# FPSModule.net
KiCad netlist of a schematic drawn in Altium Designer
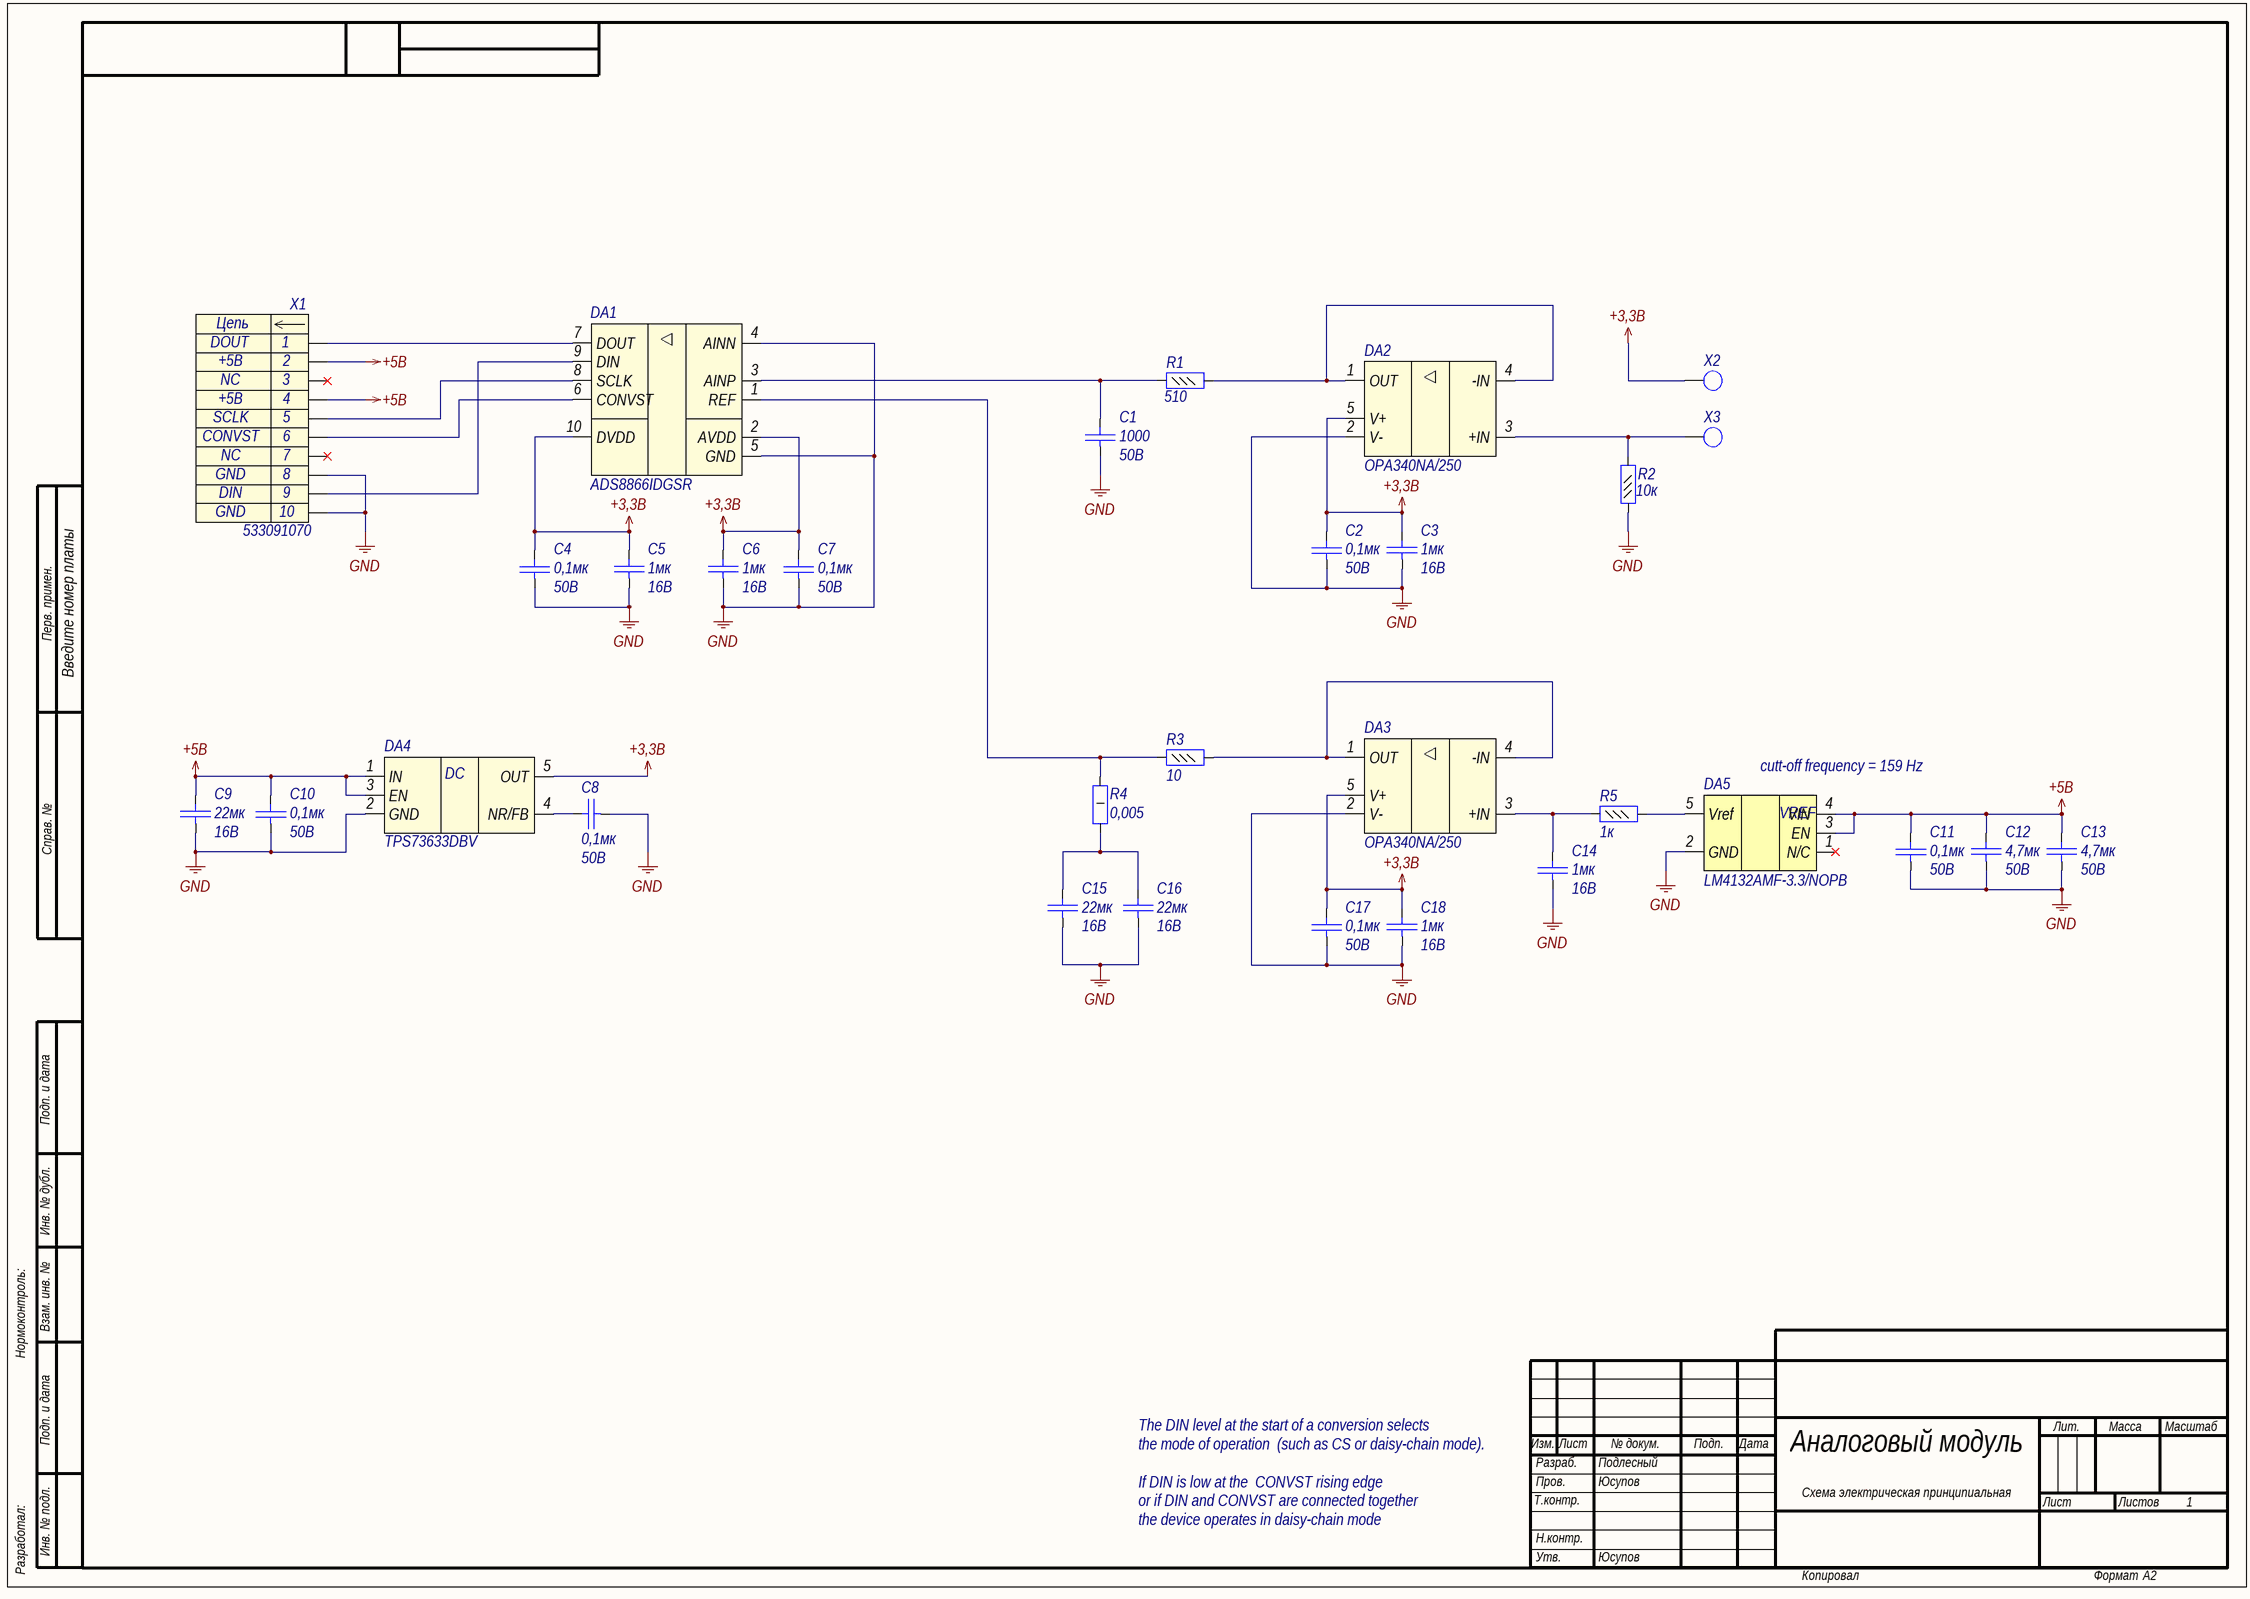
[diagram p0: FPSModule.SchDoc]

(export (version "E")
  (design (tool "Eeschema 10.0.6"))
  (components
    (comp (ref "C1")
      (value "1000")
      (footprint "C0402")
      (description "Конденсатор")
      (fields (field (name "VOLTAGE") "50B") (field (name "PART NUMBER") "GRM1555C1H102J"))
      (libsource (lib "MOP44") (part "Capacitor"))
    )
    (comp (ref "C2")
      (value "0,1мк")
      (footprint "C0402")
      (description "Конденсатор")
      (fields (field (name "VOLTAGE") "50В") (field (name "PART NUMBER") "GRM155R71H104KE14D"))
      (libsource (lib "MOP44") (part "Capacitor"))
    )
    (comp (ref "C3")
      (value "1мк")
      (footprint "C0603")
      (description "Конденсатор")
      (fields (field (name "VOLTAGE") "16B") (field (name "PART NUMBER") "GRM188R71C105KA12D**"))
      (libsource (lib "MOP44") (part "Capacitor"))
    )
    (comp (ref "C4")
      (value "0,1мк")
      (footprint "C0402")
      (description "Конденсатор")
      (fields (field (name "VOLTAGE") "50В") (field (name "PART NUMBER") "GRM155R71H104KE14D"))
      (libsource (lib "MOP44") (part "Capacitor"))
    )
    (comp (ref "C5")
      (value "1мк")
      (footprint "C0603")
      (description "Конденсатор")
      (fields (field (name "VOLTAGE") "16B") (field (name "PART NUMBER") "GRM188R71C105KA12D**"))
      (libsource (lib "MOP44") (part "Capacitor"))
    )
    (comp (ref "C6")
      (value "1мк")
      (footprint "C0603")
      (description "Конденсатор")
      (fields (field (name "VOLTAGE") "16B") (field (name "PART NUMBER") "GRM188R71C105KA12D**"))
      (libsource (lib "MOP44") (part "Capacitor"))
    )
    (comp (ref "C7")
      (value "0,1мк")
      (footprint "C0402")
      (description "Конденсатор")
      (fields (field (name "VOLTAGE") "50В") (field (name "PART NUMBER") "GRM155R71H104KE14D"))
      (libsource (lib "MOP44") (part "Capacitor"))
    )
    (comp (ref "C8")
      (value "0,1мк")
      (footprint "C0402")
      (description "Конденсатор")
      (fields (field (name "VOLTAGE") "50В") (field (name "PART NUMBER") "GRM155R71H104KE14D"))
      (libsource (lib "MOP44") (part "Capacitor"))
    )
    (comp (ref "C9")
      (value "22мк")
      (footprint "C1210")
      (description "Конденсатор")
      (fields (field (name "VOLTAGE") "16B") (field (name "PART NUMBER") "C3225X7R1C226M"))
      (libsource (lib "MOP44") (part "Capacitor"))
    )
    (comp (ref "C10")
      (value "0,1мк")
      (footprint "C0402")
      (description "Конденсатор")
      (fields (field (name "VOLTAGE") "50В") (field (name "PART NUMBER") "GRM155R71H104KE14D"))
      (libsource (lib "MOP44") (part "Capacitor"))
    )
    (comp (ref "C11")
      (value "0,1мк")
      (footprint "C0402")
      (description "Конденсатор")
      (fields (field (name "VOLTAGE") "50В") (field (name "PART NUMBER") "GRM155R71H104KE14D"))
      (libsource (lib "MOP44") (part "Capacitor"))
    )
    (comp (ref "C12")
      (value "4,7мк")
      (footprint "C0805")
      (description "Конденсатор")
      (fields (field (name "VOLTAGE") "50В") (field (name "PART NUMBER") "GRM21BZ71H475KE15L"))
      (libsource (lib "MOP44") (part "Capacitor"))
    )
    (comp (ref "C13")
      (value "4,7мк")
      (footprint "C0805")
      (description "Конденсатор")
      (fields (field (name "VOLTAGE") "50В") (field (name "PART NUMBER") "GRM21BZ71H475KE15L"))
      (libsource (lib "MOP44") (part "Capacitor"))
    )
    (comp (ref "C14")
      (value "1мк")
      (footprint "C0603")
      (description "Конденсатор")
      (fields (field (name "VOLTAGE") "16B") (field (name "PART NUMBER") "GRM188R71C105KA12D**"))
      (libsource (lib "MOP44") (part "Capacitor"))
    )
    (comp (ref "C15")
      (value "22мк")
      (footprint "C1210")
      (description "Конденсатор")
      (fields (field (name "VOLTAGE") "16B") (field (name "PART NUMBER") "C3225X7R1C226M"))
      (libsource (lib "MOP44") (part "Capacitor"))
    )
    (comp (ref "C16")
      (value "22мк")
      (footprint "C1210")
      (description "Конденсатор")
      (fields (field (name "VOLTAGE") "16B") (field (name "PART NUMBER") "C3225X7R1C226M"))
      (libsource (lib "MOP44") (part "Capacitor"))
    )
    (comp (ref "C17")
      (value "0,1мк")
      (footprint "C0402")
      (description "Конденсатор")
      (fields (field (name "VOLTAGE") "50В") (field (name "PART NUMBER") "GRM155R71H104KE14D"))
      (libsource (lib "MOP44") (part "Capacitor"))
    )
    (comp (ref "C18")
      (value "1мк")
      (footprint "C0603")
      (description "Конденсатор")
      (fields (field (name "VOLTAGE") "16B") (field (name "PART NUMBER") "GRM188R71C105KA12D**"))
      (libsource (lib "MOP44") (part "Capacitor"))
    )
    (comp (ref "DA1")
      (value "ADS8866")
      (footprint "MSOP10")
      (description "100-kSPS, serial interface, micropower, miniature,  single-ended input, SAR")
      (fields (field (name "PART NUMBER") "ADS8866IDGSR"))
      (libsource (lib "MOP44") (part "ADS8866"))
    )
    (comp (ref "DA2")
      (value "OPA340")
      (footprint "SOT23-5")
      (description "Operational Amplifiers\r\nMicroAmplifier")
      (fields (field (name "PART NUMBER") "OPA340NA/250"))
      (libsource (lib "MOP44") (part "OPA340"))
    )
    (comp (ref "DA3")
      (value "OPA340")
      (footprint "SOT23-5")
      (description "Operational Amplifiers\r\nMicroAmplifier")
      (fields (field (name "PART NUMBER") "OPA340NA/250"))
      (libsource (lib "MOP44") (part "OPA340"))
    )
    (comp (ref "DA4")
      (value "TPS736DBV")
      (footprint "SOT23-5")
      (description "400-mA Low-Dropout Regulator with Reverse Current  Protection")
      (fields (field (name "PART NUMBER") "TPS73633DBV") (field (name "MANUFACTURER") "Texas Instruments"))
      (libsource (lib "MOP44") (part "TPS736DBV"))
    )
    (comp (ref "DA5")
      (value "LM4132")
      (footprint "SOT23-5")
      (description "Precision Low Dropout Voltage Reference")
      (fields
        (field (name "PART NUMBER") "LM4132AMF-3.3/NOPB")
        (field (name "MANUFACTURER") "Texas Instruments")
      )
      (libsource (lib "MOP44") (part "LM4132"))
    )
    (comp (ref "R1")
      (value "510")
      (footprint "R0402")
      (description "Резистор")
      (fields (field (name "PART NUMBER") "RC0402FR-07510RL") (field (name "POWER") "0,062Вт"))
      (libsource (lib "MOP44") (part "Resistor_0,062Вт"))
    )
    (comp (ref "R2")
      (value "10к")
      (footprint "R0402")
      (description "Резистор")
      (fields (field (name "PART NUMBER") "RC0402FR-0710KL") (field (name "POWER") "0,062Вт"))
      (libsource (lib "") (part "Resistor_0,062Вт_1"))
    )
    (comp (ref "R3")
      (value "10")
      (footprint "R0402")
      (description "Резистор")
      (fields (field (name "PART NUMBER") "RC0402FR-0710RL") (field (name "POWER") "0,062Вт"))
      (libsource (lib "MOP44") (part "Resistor_0,062Вт"))
    )
    (comp (ref "R4")
      (value "0,005")
      (footprint "R1206")
      (description "Резистор")
      (fields (field (name "PART NUMBER") "CSRF1206FT5L00") (field (name "POWER") "1Вт"))
      (libsource (lib "MOP44") (part "Resistor_1Вт"))
    )
    (comp (ref "R5")
      (value "1к")
      (footprint "R0402")
      (description "Резистор")
      (fields (field (name "PART NUMBER") "RC0402FR-071KL") (field (name "POWER") "0,062Вт"))
      (libsource (lib "MOP44") (part "Resistor_0,062Вт"))
    )
    (comp (ref "X1")
      (value "Header_10_plg")
      (footprint "SlimStack-10pin-angl-plg")
      (description "Разъем - 10 конт. вилка")
      (fields (field (name "PART NUMBER") "533091070"))
      (libsource (lib "MOP44") (part "Header_10_plg"))
    )
    (comp (ref "X2") (value "SoldPoint") (footprint "SOLD_1PAD") (libsource (lib "MOP44") (part "SoldPoint")))
    (comp (ref "X3") (value "SoldPoint") (footprint "SOLD_1PAD") (libsource (lib "MOP44") (part "SoldPoint")))
  )
  (nets
    (net (code "1") (name "+3,3B") (class "Default")
      (node (ref "C17") (pin "2") (pinfunction "2_2") (pintype "passive"))
      (node (ref "C18") (pin "2") (pinfunction "2_2") (pintype "passive"))
      (node (ref "C2") (pin "2") (pinfunction "2_2") (pintype "passive"))
      (node (ref "C3") (pin "2") (pinfunction "2_2") (pintype "passive"))
      (node (ref "C4") (pin "2") (pinfunction "2_2") (pintype "passive"))
      (node (ref "C5") (pin "2") (pinfunction "2_2") (pintype "passive"))
      (node (ref "C6") (pin "2") (pinfunction "2_2") (pintype "passive"))
      (node (ref "C7") (pin "2") (pinfunction "2_2") (pintype "passive"))
      (node (ref "DA1") (pin "10") (pinfunction "DVDD_10") (pintype "passive"))
      (node (ref "DA1") (pin "2") (pinfunction "AVDD_2") (pintype "passive"))
      (node (ref "DA2") (pin "5") (pinfunction "V+_5") (pintype "passive"))
      (node (ref "DA3") (pin "5") (pinfunction "V+_5") (pintype "passive"))
      (node (ref "DA4") (pin "5") (pinfunction "OUT_5") (pintype "power_in"))
      (node (ref "X2") (pin "1") (pinfunction "1_1") (pintype "passive"))
    )
    (net (code "2") (name "+5B") (class "Default")
      (node (ref "C10") (pin "2") (pinfunction "2_2") (pintype "passive"))
      (node (ref "C11") (pin "2") (pinfunction "2_2") (pintype "passive"))
      (node (ref "C12") (pin "2") (pinfunction "2_2") (pintype "passive"))
      (node (ref "C13") (pin "2") (pinfunction "2_2") (pintype "passive"))
      (node (ref "C9") (pin "2") (pinfunction "2_2") (pintype "passive"))
      (node (ref "DA4") (pin "1") (pinfunction "IN_1") (pintype "power_in"))
      (node (ref "DA4") (pin "3") (pinfunction "EN_3") (pintype "power_in"))
      (node (ref "DA5") (pin "3") (pinfunction "EN_3") (pintype "passive"))
      (node (ref "DA5") (pin "4") (pinfunction "VIN_4") (pintype "passive"))
      (node (ref "X1") (pin "2") (pinfunction "2_2") (pintype "passive"))
      (node (ref "X1") (pin "4") (pinfunction "4_4") (pintype "passive"))
    )
    (net (code "3") (name "GND") (class "Default")
      (node (ref "C1") (pin "1") (pinfunction "1_1") (pintype "passive"))
      (node (ref "C10") (pin "1") (pinfunction "1_1") (pintype "passive"))
      (node (ref "C11") (pin "1") (pinfunction "1_1") (pintype "passive"))
      (node (ref "C12") (pin "1") (pinfunction "1_1") (pintype "passive"))
      (node (ref "C13") (pin "1") (pinfunction "1_1") (pintype "passive"))
      (node (ref "C14") (pin "1") (pinfunction "1_1") (pintype "passive"))
      (node (ref "C15") (pin "1") (pinfunction "1_1") (pintype "passive"))
      (node (ref "C16") (pin "1") (pinfunction "1_1") (pintype "passive"))
      (node (ref "C17") (pin "1") (pinfunction "1_1") (pintype "passive"))
      (node (ref "C18") (pin "1") (pinfunction "1_1") (pintype "passive"))
      (node (ref "C2") (pin "1") (pinfunction "1_1") (pintype "passive"))
      (node (ref "C3") (pin "1") (pinfunction "1_1") (pintype "passive"))
      (node (ref "C4") (pin "1") (pinfunction "1_1") (pintype "passive"))
      (node (ref "C5") (pin "1") (pinfunction "1_1") (pintype "passive"))
      (node (ref "C6") (pin "1") (pinfunction "1_1") (pintype "passive"))
      (node (ref "C7") (pin "1") (pinfunction "1_1") (pintype "passive"))
      (node (ref "C8") (pin "1") (pinfunction "1_1") (pintype "passive"))
      (node (ref "C9") (pin "1") (pinfunction "1_1") (pintype "passive"))
      (node (ref "DA1") (pin "4") (pinfunction "AINN_4") (pintype "passive"))
      (node (ref "DA1") (pin "5") (pinfunction "GND_5") (pintype "passive"))
      (node (ref "DA2") (pin "2") (pinfunction "V-_2") (pintype "passive"))
      (node (ref "DA3") (pin "2") (pinfunction "V-_2") (pintype "passive"))
      (node (ref "DA4") (pin "2") (pinfunction "GND_2") (pintype "power_in"))
      (node (ref "DA5") (pin "2") (pinfunction "GND_2") (pintype "passive"))
      (node (ref "R2") (pin "1") (pinfunction "1_1") (pintype "passive"))
      (node (ref "X1") (pin "10") (pinfunction "10_10") (pintype "passive"))
      (node (ref "X1") (pin "8") (pinfunction "8_8") (pintype "passive"))
    )
    (net (code "4") (name "Net-(C15-Pad2)") (class "Default")
      (node (ref "C15") (pin "2") (pinfunction "2_2") (pintype "passive"))
      (node (ref "C16") (pin "2") (pinfunction "2_2") (pintype "passive"))
      (node (ref "R4") (pin "1") (pinfunction "1_1") (pintype "passive"))
    )
    (net (code "5") (name "Net-(DA1-AINP)") (class "Default")
      (node (ref "C1") (pin "2") (pinfunction "2_2") (pintype "passive"))
      (node (ref "DA1") (pin "3") (pinfunction "AINP_3") (pintype "passive"))
      (node (ref "R1") (pin "1") (pinfunction "1_1") (pintype "passive"))
    )
    (net (code "6") (name "Net-(DA1-CONVST)") (class "Default")
      (node (ref "DA1") (pin "6") (pinfunction "CONVST_6") (pintype "passive"))
      (node (ref "X1") (pin "6") (pinfunction "6_6") (pintype "passive"))
    )
    (net (code "7") (name "Net-(DA1-DIN)") (class "Default")
      (node (ref "DA1") (pin "9") (pinfunction "DIN_9") (pintype "passive"))
      (node (ref "X1") (pin "9") (pinfunction "9_9") (pintype "passive"))
    )
    (net (code "8") (name "Net-(DA1-DOUT)") (class "Default")
      (node (ref "DA1") (pin "7") (pinfunction "DOUT_7") (pintype "passive"))
      (node (ref "X1") (pin "1") (pinfunction "1_1") (pintype "passive"))
    )
    (net (code "9") (name "Net-(DA1-REF)") (class "Default")
      (node (ref "DA1") (pin "1") (pinfunction "REF_1") (pintype "passive"))
      (node (ref "R3") (pin "1") (pinfunction "1_1") (pintype "passive"))
      (node (ref "R4") (pin "2") (pinfunction "5_2") (pintype "passive"))
    )
    (net (code "10") (name "Net-(DA1-SCLK)") (class "Default")
      (node (ref "DA1") (pin "8") (pinfunction "SCLK_8") (pintype "passive"))
      (node (ref "X1") (pin "5") (pinfunction "5_5") (pintype "passive"))
    )
    (net (code "11") (name "Net-(DA2-+IN)") (class "Default")
      (node (ref "DA2") (pin "3") (pinfunction "+IN_3") (pintype "passive"))
      (node (ref "R2") (pin "2") (pinfunction "2_2") (pintype "passive"))
      (node (ref "X3") (pin "1") (pinfunction "1_1") (pintype "passive"))
    )
    (net (code "12") (name "Net-(DA2--IN)") (class "Default")
      (node (ref "DA2") (pin "1") (pinfunction "OUT_1") (pintype "passive"))
      (node (ref "DA2") (pin "4") (pinfunction "-IN_4") (pintype "passive"))
      (node (ref "R1") (pin "2") (pinfunction "2_2") (pintype "passive"))
    )
    (net (code "13") (name "Net-(DA3-+IN)") (class "Default")
      (node (ref "C14") (pin "2") (pinfunction "2_2") (pintype "passive"))
      (node (ref "DA3") (pin "3") (pinfunction "+IN_3") (pintype "passive"))
      (node (ref "R5") (pin "1") (pinfunction "1_1") (pintype "passive"))
    )
    (net (code "14") (name "Net-(DA3--IN)") (class "Default")
      (node (ref "DA3") (pin "1") (pinfunction "OUT_1") (pintype "passive"))
      (node (ref "DA3") (pin "4") (pinfunction "-IN_4") (pintype "passive"))
      (node (ref "R3") (pin "2") (pinfunction "2_2") (pintype "passive"))
    )
    (net (code "15") (name "Net-(DA4-NR{slash}FB)") (class "Default")
      (node (ref "C8") (pin "2") (pinfunction "2_2") (pintype "passive"))
      (node (ref "DA4") (pin "4") (pinfunction "NR/FB_4") (pintype "power_in"))
    )
    (net (code "16") (name "Net-(DA5-Vref)") (class "Default")
      (node (ref "DA5") (pin "5") (pinfunction "Vref_5") (pintype "passive"))
      (node (ref "R5") (pin "2") (pinfunction "2_2") (pintype "passive"))
    )
    (net (code "17") (name "unconnected-(DA5-N{slash}C-Pad1)") (class "Default")
      (node (ref "DA5") (pin "1") (pinfunction "N/C_1") (pintype "passive+no_connect"))
    )
    (net (code "18") (name "unconnected-(X1-Pad3)") (class "Default")
      (node (ref "X1") (pin "3") (pinfunction "3_3") (pintype "passive+no_connect"))
    )
    (net (code "19") (name "unconnected-(X1-Pad7)") (class "Default")
      (node (ref "X1") (pin "7") (pinfunction "7_7") (pintype "passive+no_connect"))
    )
  )
)
